# Adafruit_OLED_FeatherWing.net
KiCad netlist of a schematic drawn in EAGLE
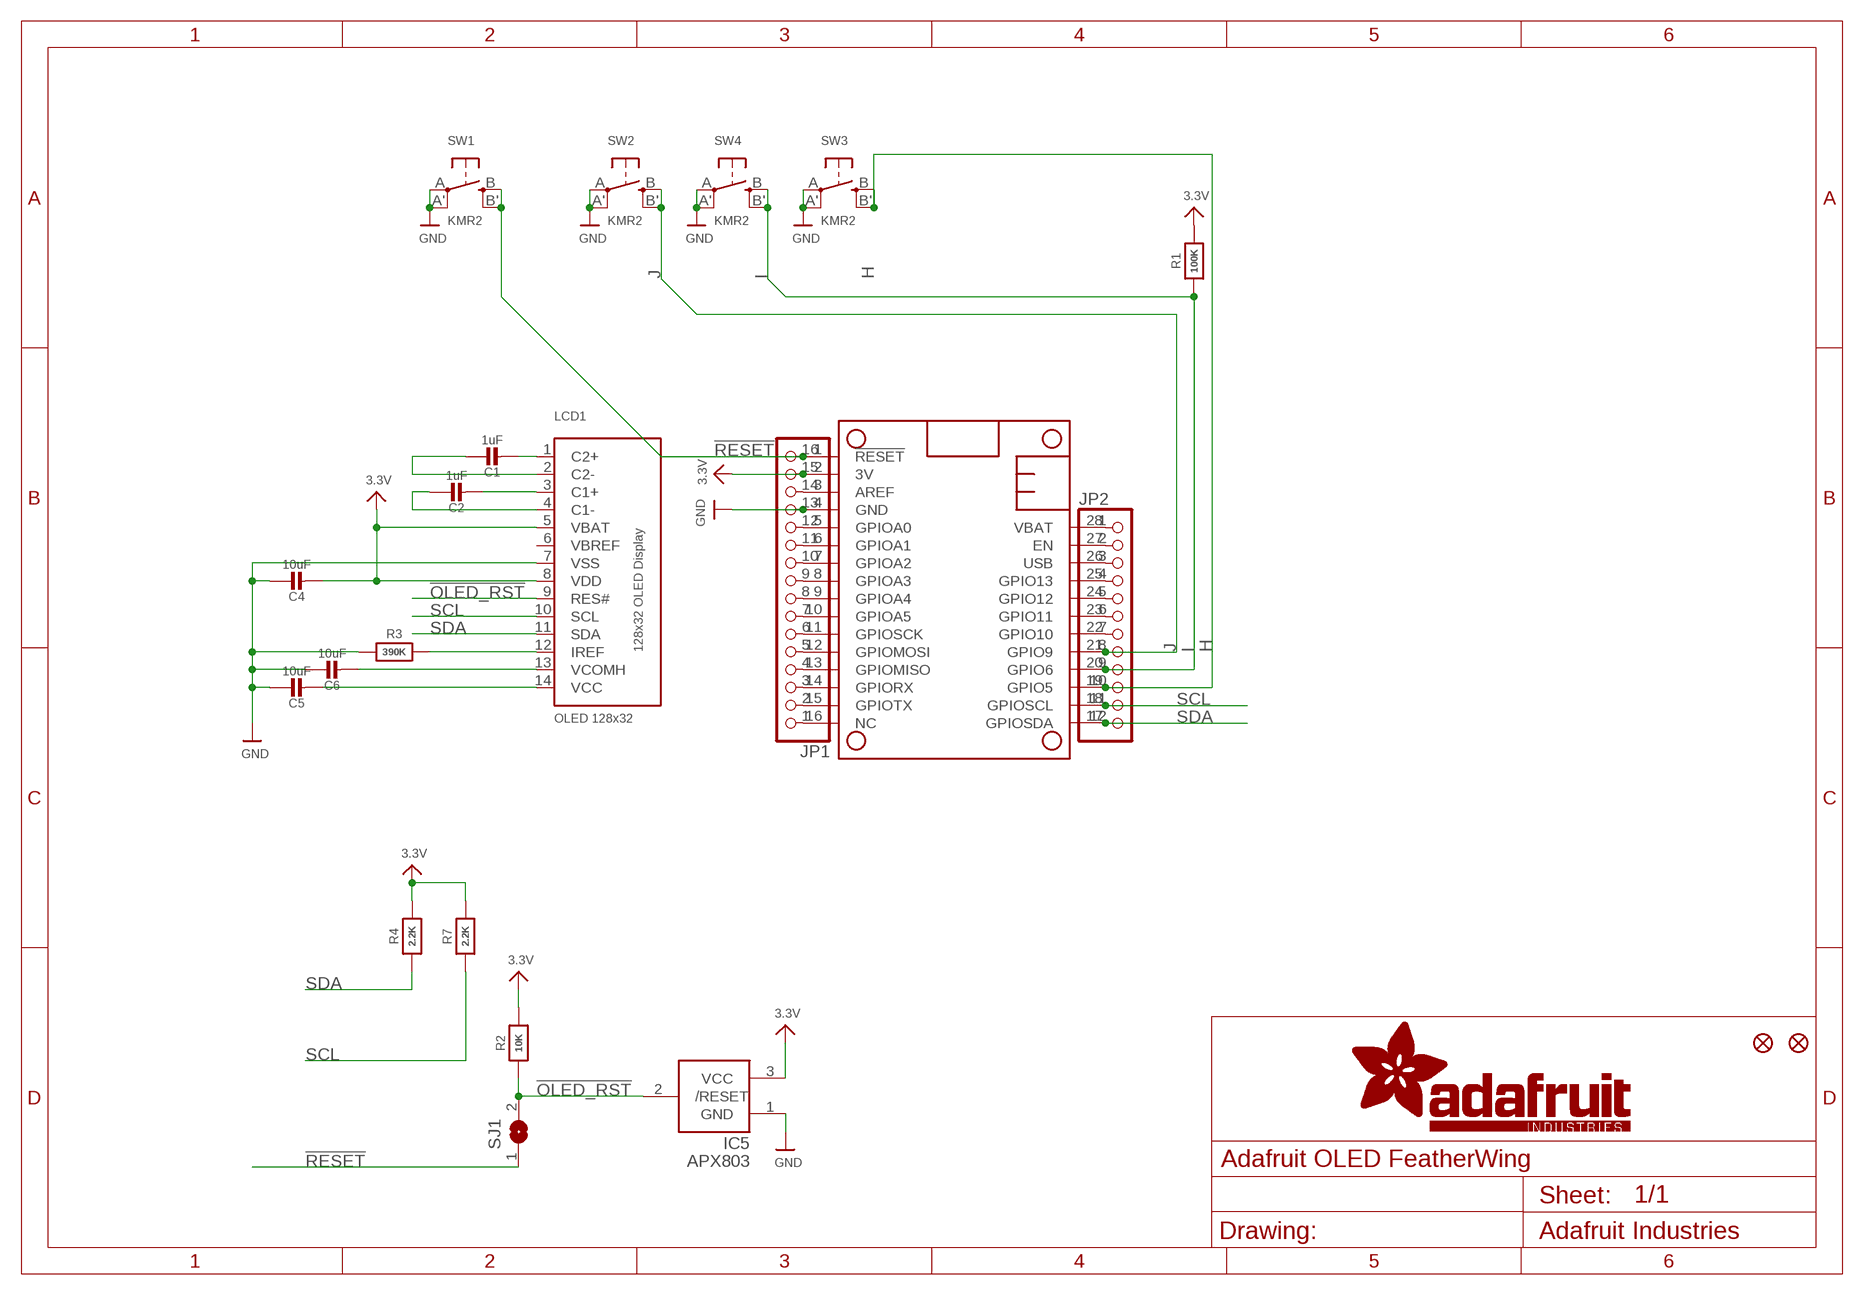
[diagram p0: schematic, sheet 1]

(export (version "E")
  (design (tool "Eeschema 10.0.6"))
  (components
    (comp (ref "C1")
      (value "1uF")
      (footprint "eagle-import:0805-NO")
      (libsource (lib "eagle-import") (part "CAP_CERAMIC0805-NOOUTLINE"))
    )
    (comp (ref "C2")
      (value "1uF")
      (footprint "eagle-import:0805-NO")
      (libsource (lib "eagle-import") (part "CAP_CERAMIC0805-NOOUTLINE"))
    )
    (comp (ref "C4")
      (value "10uF")
      (footprint "eagle-import:0805-NO")
      (libsource (lib "eagle-import") (part "CAP_CERAMIC0805-NOOUTLINE"))
    )
    (comp (ref "C5")
      (value "10uF")
      (footprint "eagle-import:0805-NO")
      (libsource (lib "eagle-import") (part "CAP_CERAMIC0805-NOOUTLINE"))
    )
    (comp (ref "C6")
      (value "10uF")
      (footprint "eagle-import:0805-NO")
      (libsource (lib "eagle-import") (part "CAP_CERAMIC0805-NOOUTLINE"))
    )
    (comp (ref "FID1")
      (value "FIDUCIAL\"\"")
      (footprint "eagle-import:FIDUCIAL_1MM")
      (libsource (lib "eagle-import") (part "FIDUCIAL{dblquote}{dblquote}"))
    )
    (comp (ref "FID2")
      (value "FIDUCIAL\"\"")
      (footprint "eagle-import:FIDUCIAL_1MM")
      (libsource (lib "eagle-import") (part "FIDUCIAL{dblquote}{dblquote}"))
    )
    (comp (ref "IC5")
      (value "APX803")
      (footprint "eagle-import:SOT23")
      (libsource (lib "eagle-import") (part "AXP083-SAG"))
    )
    (comp (ref "JP1")
      (value "HEADER-1X16ROUND")
      (footprint "eagle-import:1X16_ROUND")
      (libsource (lib "eagle-import") (part "HEADER-1X16ROUND"))
    )
    (comp (ref "JP2")
      (value "HEADER-1X12")
      (footprint "eagle-import:1X12_ROUND")
      (libsource (lib "eagle-import") (part "HEADER-1X12"))
    )
    (comp (ref "LCD1")
      (value "OLED 128x32")
      (footprint "eagle-import:UG-2832HSWEG02_WRAPUNDER")
      (libsource (lib "eagle-import") (part "DISP_OLED_UG-2832HSWEG02"))
    )
    (comp (ref "MS1")
      (value "FEATHERWING")
      (footprint "eagle-import:FEATHERWING")
      (libsource (lib "eagle-import") (part "FEATHERWING"))
    )
    (comp (ref "R1")
      (value "100K")
      (footprint "eagle-import:0805-NO")
      (libsource (lib "eagle-import") (part "RESISTOR0805_NOOUTLINE"))
    )
    (comp (ref "R2")
      (value "10K")
      (footprint "eagle-import:_0805MP")
      (libsource (lib "eagle-import") (part "RESISTOR_0805MP"))
    )
    (comp (ref "R3")
      (value "390K")
      (footprint "eagle-import:0805-NO")
      (libsource (lib "eagle-import") (part "RESISTOR0805_NOOUTLINE"))
    )
    (comp (ref "R4")
      (value "2.2K")
      (footprint "eagle-import:0805-NO")
      (libsource (lib "eagle-import") (part "RESISTOR0805_NOOUTLINE"))
    )
    (comp (ref "R7")
      (value "2.2K")
      (footprint "eagle-import:0805-NO")
      (libsource (lib "eagle-import") (part "RESISTOR0805_NOOUTLINE"))
    )
    (comp (ref "SJ1")
      (value "SOLDERJUMPER")
      (footprint "eagle-import:SOLDERJUMPER_ARROW_NOPASTE")
      (libsource (lib "eagle-import") (part "SOLDERJUMPER"))
    )
    (comp (ref "SW1")
      (value "KMR2")
      (footprint "eagle-import:BTN_KMR2_4.6X2.8")
      (libsource (lib "eagle-import") (part "SWITCH_TACT_SMT4.6X2.8"))
    )
    (comp (ref "SW2")
      (value "KMR2")
      (footprint "eagle-import:BTN_KMR2_4.6X2.8")
      (libsource (lib "eagle-import") (part "SWITCH_TACT_SMT4.6X2.8"))
    )
    (comp (ref "SW3")
      (value "KMR2")
      (footprint "eagle-import:BTN_KMR2_4.6X2.8")
      (libsource (lib "eagle-import") (part "SWITCH_TACT_SMT4.6X2.8"))
    )
    (comp (ref "SW4")
      (value "KMR2")
      (footprint "eagle-import:BTN_KMR2_4.6X2.8")
      (libsource (lib "eagle-import") (part "SWITCH_TACT_SMT4.6X2.8"))
    )
  )
  (nets
    (net (code "1") (name "/H") (class "Default")
      (node (ref "JP2") (pin "10") (pinfunction "10_10") (pintype "passive"))
      (node (ref "MS1") (pin "19") (pinfunction "GPIO5_19") (pintype "bidirectional"))
      (node (ref "SW3") (pin "B") (pinfunction "S_B") (pintype "passive"))
      (node (ref "SW3") (pin "B'") (pinfunction "S1_B'") (pintype "passive"))
    )
    (net (code "2") (name "/I") (class "Default")
      (node (ref "JP2") (pin "9") (pinfunction "9_9") (pintype "passive"))
      (node (ref "MS1") (pin "20") (pinfunction "GPIO6_20") (pintype "bidirectional"))
      (node (ref "R1") (pin "1") (pinfunction "1_1") (pintype "passive"))
      (node (ref "SW4") (pin "B") (pinfunction "S_B") (pintype "passive"))
      (node (ref "SW4") (pin "B'") (pinfunction "S1_B'") (pintype "passive"))
    )
    (net (code "3") (name "/J") (class "Default")
      (node (ref "JP2") (pin "8") (pinfunction "8_8") (pintype "passive"))
      (node (ref "MS1") (pin "21") (pinfunction "GPIO9_21") (pintype "bidirectional"))
      (node (ref "SW2") (pin "B") (pinfunction "S_B") (pintype "passive"))
      (node (ref "SW2") (pin "B'") (pinfunction "S1_B'") (pintype "passive"))
    )
    (net (code "4") (name "/SCL") (class "Default")
      (node (ref "JP2") (pin "11") (pinfunction "11_11") (pintype "passive"))
      (node (ref "LCD1") (pin "10") (pinfunction "SCL_10") (pintype "bidirectional"))
      (node (ref "MS1") (pin "18") (pinfunction "GPIOSCL_18") (pintype "bidirectional"))
      (node (ref "R7") (pin "1") (pinfunction "1_1") (pintype "passive"))
    )
    (net (code "5") (name "/SDA") (class "Default")
      (node (ref "JP2") (pin "12") (pinfunction "12_12") (pintype "passive"))
      (node (ref "LCD1") (pin "11") (pinfunction "SDA_11") (pintype "bidirectional"))
      (node (ref "MS1") (pin "17") (pinfunction "GPIOSDA_17") (pintype "bidirectional"))
      (node (ref "R4") (pin "1") (pinfunction "1_1") (pintype "passive"))
    )
    (net (code "6") (name "/VBREF") (class "Default")
      (node (ref "LCD1") (pin "6") (pinfunction "VBREF_6") (pintype "power_in"))
    )
    (net (code "7") (name "/~{OLED_RST}") (class "Default")
      (node (ref "IC5") (pin "2") (pinfunction "/RESET_2") (pintype "output"))
      (node (ref "LCD1") (pin "9") (pinfunction "RES#_9") (pintype "bidirectional"))
      (node (ref "R2") (pin "1") (pinfunction "1_1") (pintype "passive"))
      (node (ref "SJ1") (pin "2") (pinfunction "2_2") (pintype "passive"))
    )
    (net (code "8") (name "/~{RESET}") (class "Default")
      (node (ref "JP1") (pin "16") (pinfunction "16_16") (pintype "passive"))
      (node (ref "MS1") (pin "1") (pinfunction "~{RESET}_1") (pintype "input"))
      (node (ref "SJ1") (pin "1") (pinfunction "1_1") (pintype "passive"))
      (node (ref "SW1") (pin "B") (pinfunction "S_B") (pintype "passive"))
      (node (ref "SW1") (pin "B'") (pinfunction "S1_B'") (pintype "passive"))
    )
    (net (code "9") (name "3.3V") (class "Default")
      (node (ref "C4") (pin "2") (pinfunction "2_2") (pintype "passive"))
      (node (ref "IC5") (pin "3") (pinfunction "VCC_3") (pintype "power_in"))
      (node (ref "JP1") (pin "15") (pinfunction "15_15") (pintype "passive"))
      (node (ref "LCD1") (pin "5") (pinfunction "VBAT_5") (pintype "power_in"))
      (node (ref "LCD1") (pin "8") (pinfunction "VDD_8") (pintype "power_in"))
      (node (ref "MS1") (pin "2") (pinfunction "3V_2") (pintype "power_in"))
      (node (ref "R1") (pin "2") (pinfunction "2_2") (pintype "passive"))
      (node (ref "R2") (pin "2") (pinfunction "2_2") (pintype "passive"))
      (node (ref "R4") (pin "2") (pinfunction "2_2") (pintype "passive"))
      (node (ref "R7") (pin "2") (pinfunction "2_2") (pintype "passive"))
    )
    (net (code "10") (name "GND") (class "Default")
      (node (ref "C4") (pin "1") (pinfunction "1_1") (pintype "passive"))
      (node (ref "C5") (pin "1") (pinfunction "1_1") (pintype "passive"))
      (node (ref "C6") (pin "1") (pinfunction "1_1") (pintype "passive"))
      (node (ref "IC5") (pin "1") (pinfunction "GND_1") (pintype "power_in"))
      (node (ref "JP1") (pin "13") (pinfunction "13_13") (pintype "passive"))
      (node (ref "LCD1") (pin "7") (pinfunction "VSS_7") (pintype "power_in"))
      (node (ref "MS1") (pin "4") (pinfunction "GND_4") (pintype "power_in"))
      (node (ref "R3") (pin "1") (pinfunction "1_1") (pintype "passive"))
      (node (ref "SW1") (pin "A") (pinfunction "P_A") (pintype "passive"))
      (node (ref "SW1") (pin "A'") (pinfunction "P1_A'") (pintype "passive"))
      (node (ref "SW2") (pin "A") (pinfunction "P_A") (pintype "passive"))
      (node (ref "SW2") (pin "A'") (pinfunction "P1_A'") (pintype "passive"))
      (node (ref "SW3") (pin "A") (pinfunction "P_A") (pintype "passive"))
      (node (ref "SW3") (pin "A'") (pinfunction "P1_A'") (pintype "passive"))
      (node (ref "SW4") (pin "A") (pinfunction "P_A") (pintype "passive"))
      (node (ref "SW4") (pin "A'") (pinfunction "P1_A'") (pintype "passive"))
    )
    (net (code "11") (name "Net-(LCD1-C1+)") (class "Default")
      (node (ref "C2") (pin "2") (pinfunction "2_2") (pintype "passive"))
      (node (ref "LCD1") (pin "3") (pinfunction "C1+_3") (pintype "bidirectional"))
    )
    (net (code "12") (name "Net-(LCD1-C1-)") (class "Default")
      (node (ref "C2") (pin "1") (pinfunction "1_1") (pintype "passive"))
      (node (ref "LCD1") (pin "4") (pinfunction "C1-_4") (pintype "bidirectional"))
    )
    (net (code "13") (name "Net-(LCD1-C2+)") (class "Default")
      (node (ref "C1") (pin "2") (pinfunction "2_2") (pintype "passive"))
      (node (ref "LCD1") (pin "1") (pinfunction "C2+_1") (pintype "bidirectional"))
    )
    (net (code "14") (name "Net-(LCD1-C2-)") (class "Default")
      (node (ref "C1") (pin "1") (pinfunction "1_1") (pintype "passive"))
      (node (ref "LCD1") (pin "2") (pinfunction "C2-_2") (pintype "bidirectional"))
    )
    (net (code "15") (name "Net-(LCD1-IREF)") (class "Default")
      (node (ref "LCD1") (pin "12") (pinfunction "IREF_12") (pintype "bidirectional"))
      (node (ref "R3") (pin "2") (pinfunction "2_2") (pintype "passive"))
    )
    (net (code "16") (name "Net-(LCD1-VCC)") (class "Default")
      (node (ref "C5") (pin "2") (pinfunction "2_2") (pintype "passive"))
      (node (ref "LCD1") (pin "14") (pinfunction "VCC_14") (pintype "power_in"))
    )
    (net (code "17") (name "Net-(LCD1-VCOMH)") (class "Default")
      (node (ref "C6") (pin "2") (pinfunction "2_2") (pintype "passive"))
      (node (ref "LCD1") (pin "13") (pinfunction "VCOMH_13") (pintype "power_in"))
    )
    (net (code "18") (name "Net-(MS1-AREF)") (class "Default")
      (node (ref "JP1") (pin "14") (pinfunction "14_14") (pintype "passive"))
      (node (ref "MS1") (pin "3") (pinfunction "AREF_3") (pintype "passive"))
    )
    (net (code "19") (name "Net-(MS1-EN)") (class "Default")
      (node (ref "JP2") (pin "2") (pinfunction "2_2") (pintype "passive"))
      (node (ref "MS1") (pin "27") (pinfunction "EN_27") (pintype "passive"))
    )
    (net (code "20") (name "Net-(MS1-GPIO10)") (class "Default")
      (node (ref "JP2") (pin "7") (pinfunction "7_7") (pintype "passive"))
      (node (ref "MS1") (pin "22") (pinfunction "GPIO10_22") (pintype "bidirectional"))
    )
    (net (code "21") (name "Net-(MS1-GPIO11)") (class "Default")
      (node (ref "JP2") (pin "6") (pinfunction "6_6") (pintype "passive"))
      (node (ref "MS1") (pin "23") (pinfunction "GPIO11_23") (pintype "bidirectional"))
    )
    (net (code "22") (name "Net-(MS1-GPIO12)") (class "Default")
      (node (ref "JP2") (pin "5") (pinfunction "5_5") (pintype "passive"))
      (node (ref "MS1") (pin "24") (pinfunction "GPIO12_24") (pintype "bidirectional"))
    )
    (net (code "23") (name "Net-(MS1-GPIO13)") (class "Default")
      (node (ref "JP2") (pin "4") (pinfunction "4_4") (pintype "passive"))
      (node (ref "MS1") (pin "25") (pinfunction "GPIO13_25") (pintype "bidirectional"))
    )
    (net (code "24") (name "Net-(MS1-GPIOA0)") (class "Default")
      (node (ref "JP1") (pin "12") (pinfunction "12_12") (pintype "passive"))
      (node (ref "MS1") (pin "5") (pinfunction "GPIOA0_5") (pintype "bidirectional"))
    )
    (net (code "25") (name "Net-(MS1-GPIOA1)") (class "Default")
      (node (ref "JP1") (pin "11") (pinfunction "11_11") (pintype "passive"))
      (node (ref "MS1") (pin "6") (pinfunction "GPIOA1_6") (pintype "bidirectional"))
    )
    (net (code "26") (name "Net-(MS1-GPIOA2)") (class "Default")
      (node (ref "JP1") (pin "10") (pinfunction "10_10") (pintype "passive"))
      (node (ref "MS1") (pin "7") (pinfunction "GPIOA2_7") (pintype "bidirectional"))
    )
    (net (code "27") (name "Net-(MS1-GPIOA3)") (class "Default")
      (node (ref "JP1") (pin "9") (pinfunction "9_9") (pintype "passive"))
      (node (ref "MS1") (pin "8") (pinfunction "GPIOA3_8") (pintype "bidirectional"))
    )
    (net (code "28") (name "Net-(MS1-GPIOA4)") (class "Default")
      (node (ref "JP1") (pin "8") (pinfunction "8_8") (pintype "passive"))
      (node (ref "MS1") (pin "9") (pinfunction "GPIOA4_9") (pintype "bidirectional"))
    )
    (net (code "29") (name "Net-(MS1-GPIOA5)") (class "Default")
      (node (ref "JP1") (pin "7") (pinfunction "7_7") (pintype "passive"))
      (node (ref "MS1") (pin "10") (pinfunction "GPIOA5_10") (pintype "bidirectional"))
    )
    (net (code "30") (name "Net-(MS1-GPIOMISO)") (class "Default")
      (node (ref "JP1") (pin "4") (pinfunction "4_4") (pintype "passive"))
      (node (ref "MS1") (pin "13") (pinfunction "GPIOMISO_13") (pintype "bidirectional"))
    )
    (net (code "31") (name "Net-(MS1-GPIOMOSI)") (class "Default")
      (node (ref "JP1") (pin "5") (pinfunction "5_5") (pintype "passive"))
      (node (ref "MS1") (pin "12") (pinfunction "GPIOMOSI_12") (pintype "bidirectional"))
    )
    (net (code "32") (name "Net-(MS1-GPIORX)") (class "Default")
      (node (ref "JP1") (pin "3") (pinfunction "3_3") (pintype "passive"))
      (node (ref "MS1") (pin "14") (pinfunction "GPIORX_14") (pintype "bidirectional"))
    )
    (net (code "33") (name "Net-(MS1-GPIOSCK)") (class "Default")
      (node (ref "JP1") (pin "6") (pinfunction "6_6") (pintype "passive"))
      (node (ref "MS1") (pin "11") (pinfunction "GPIOSCK_11") (pintype "bidirectional"))
    )
    (net (code "34") (name "Net-(MS1-GPIOTX)") (class "Default")
      (node (ref "JP1") (pin "2") (pinfunction "2_2") (pintype "passive"))
      (node (ref "MS1") (pin "15") (pinfunction "GPIOTX_15") (pintype "bidirectional"))
    )
    (net (code "35") (name "Net-(MS1-NC)") (class "Default")
      (node (ref "JP1") (pin "1") (pinfunction "1_1") (pintype "passive"))
      (node (ref "MS1") (pin "16") (pinfunction "NC_16") (pintype "passive"))
    )
    (net (code "36") (name "Net-(MS1-USB)") (class "Default")
      (node (ref "JP2") (pin "3") (pinfunction "3_3") (pintype "passive"))
      (node (ref "MS1") (pin "26") (pinfunction "USB_26") (pintype "power_in"))
    )
    (net (code "37") (name "Net-(MS1-VBAT)") (class "Default")
      (node (ref "JP2") (pin "1") (pinfunction "1_1") (pintype "passive"))
      (node (ref "MS1") (pin "28") (pinfunction "VBAT_28") (pintype "power_in"))
    )
  )
)
